# SW6121_Demo_board.net
KiCad netlist of a schematic drawn in Altium Designer
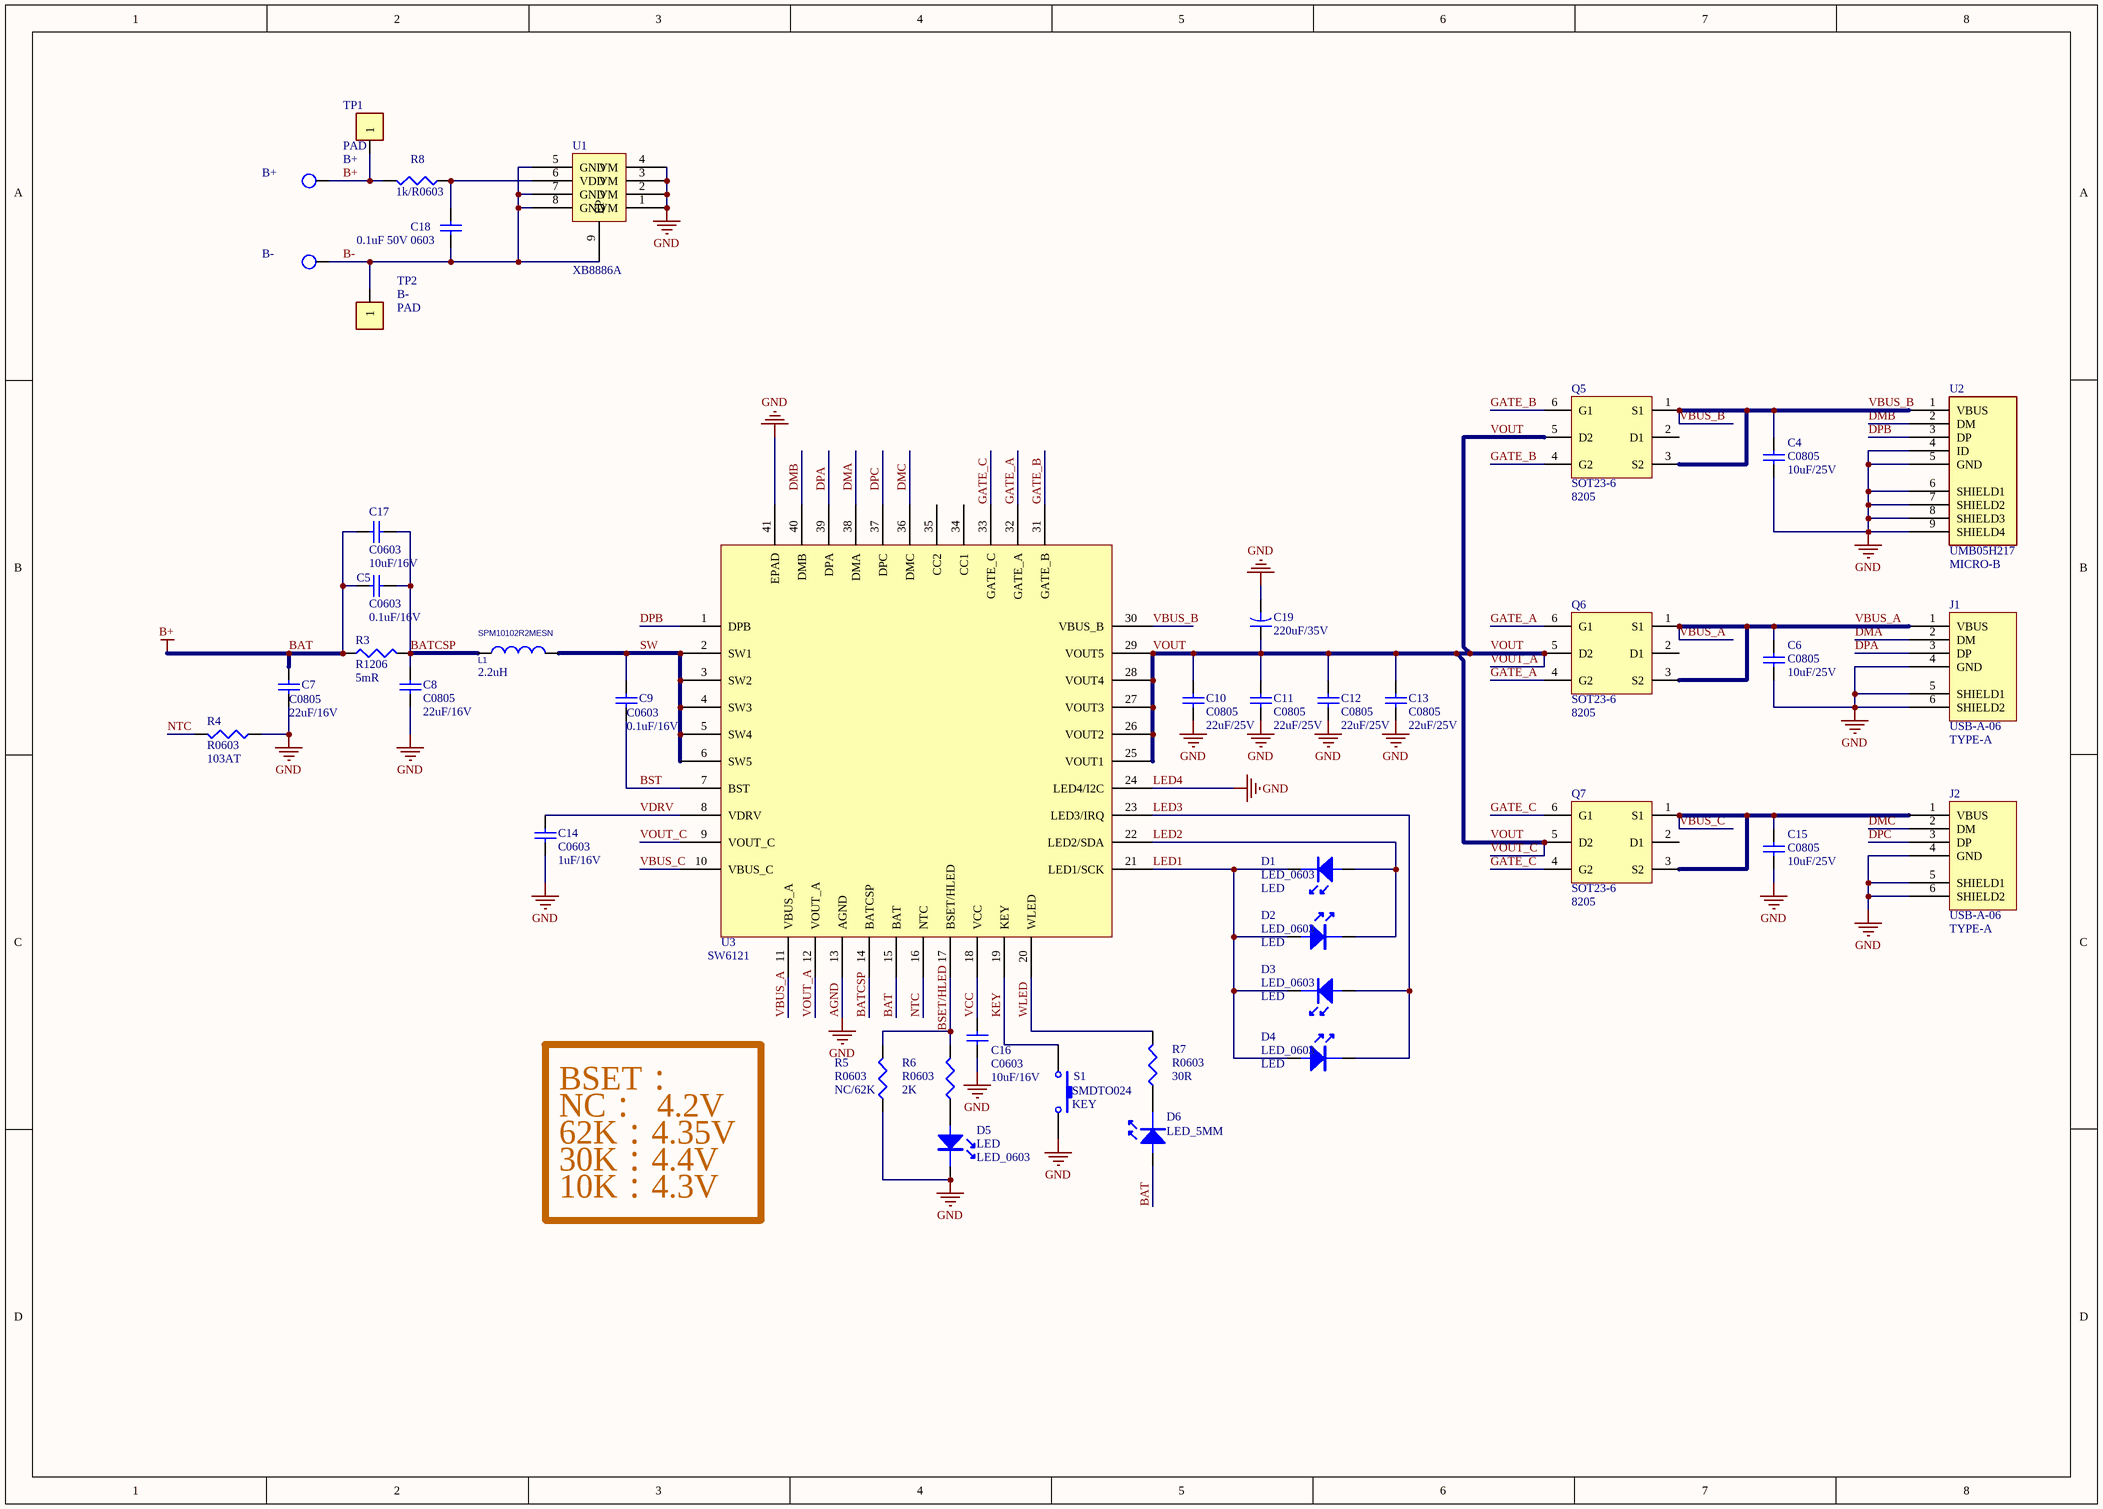
[diagram p0: SW6121 Demo board.SchDoc]

(export (version "E")
  (design (tool "Eeschema 10.0.6"))
  (components
    (comp (ref "B+") (value "PDA") (footprint "PAD") (libsource (lib "ZYX") (part "PDA")))
    (comp (ref "B-") (value "PDA") (footprint "PAD") (libsource (lib "ZYX") (part "PDA")))
    (comp (ref "C4")
      (value "C0805")
      (footprint "C0805")
      (description "Capacitor")
      (fields (field (name "ALTIUM_VALUE") "10uF/25V") (field (name "PUBLISHER") "Altium Limited"))
      (libsource (lib "*") (part "CAP0603"))
    )
    (comp (ref "C5")
      (value "C0603")
      (footprint "C0603")
      (description "Capacitor")
      (fields (field (name "ALTIUM_VALUE") "0.1uF/16V") (field (name "PUBLISHER") "Altium Limited"))
      (libsource (lib "*") (part "CAP0603"))
    )
    (comp (ref "C6")
      (value "C0805")
      (footprint "C0805")
      (description "Capacitor")
      (fields (field (name "ALTIUM_VALUE") "10uF/25V") (field (name "PUBLISHER") "Altium Limited"))
      (libsource (lib "*") (part "CAP0603"))
    )
    (comp (ref "C7")
      (value "C0805")
      (footprint "C0805")
      (description "Capacitor")
      (fields (field (name "ALTIUM_VALUE") "22uF/16V") (field (name "PUBLISHER") "Altium Limited"))
      (libsource (lib "*") (part "CAP0805"))
    )
    (comp (ref "C8")
      (value "C0805")
      (footprint "C0805")
      (description "Capacitor")
      (fields (field (name "ALTIUM_VALUE") "22uF/16V") (field (name "PUBLISHER") "Altium Limited"))
      (libsource (lib "*") (part "CAP0805"))
    )
    (comp (ref "C9")
      (value "C0603")
      (footprint "C0603")
      (description "Capacitor")
      (fields (field (name "ALTIUM_VALUE") "0.1uF/16V") (field (name "PUBLISHER") "Altium Limited"))
      (libsource (lib "*") (part "CAP0603"))
    )
    (comp (ref "C10")
      (value "C0805")
      (footprint "C0805")
      (description "Capacitor")
      (fields (field (name "ALTIUM_VALUE") "22uF/25V") (field (name "PUBLISHER") "Altium Limited"))
      (libsource (lib "*") (part "CAP0805"))
    )
    (comp (ref "C11")
      (value "C0805")
      (footprint "C0805")
      (description "Capacitor")
      (fields (field (name "ALTIUM_VALUE") "22uF/25V") (field (name "PUBLISHER") "Altium Limited"))
      (libsource (lib "*") (part "CAP0805"))
    )
    (comp (ref "C12")
      (value "C0805")
      (footprint "C0805")
      (description "Capacitor")
      (fields (field (name "ALTIUM_VALUE") "22uF/25V") (field (name "PUBLISHER") "Altium Limited"))
      (libsource (lib "*") (part "CAP0805"))
    )
    (comp (ref "C13")
      (value "C0805")
      (footprint "C0805")
      (description "Capacitor")
      (fields (field (name "ALTIUM_VALUE") "22uF/25V") (field (name "PUBLISHER") "Altium Limited"))
      (libsource (lib "*") (part "CAP0805"))
    )
    (comp (ref "C14")
      (value "C0603")
      (footprint "C0603")
      (description "Capacitor")
      (fields (field (name "ALTIUM_VALUE") "1uF/16V") (field (name "PUBLISHER") "Altium Limited"))
      (libsource (lib "*") (part "CAP0603"))
    )
    (comp (ref "C15")
      (value "C0805")
      (footprint "C0805")
      (description "Capacitor")
      (fields (field (name "ALTIUM_VALUE") "10uF/25V") (field (name "PUBLISHER") "Altium Limited"))
      (libsource (lib "*") (part "CAP0603"))
    )
    (comp (ref "C16")
      (value "C0603")
      (footprint "C0603")
      (description "Capacitor")
      (fields (field (name "ALTIUM_VALUE") "10uF/16V") (field (name "PUBLISHER") "Altium Limited"))
      (libsource (lib "*") (part "CAP0603"))
    )
    (comp (ref "C17")
      (value "C0603")
      (footprint "C0603")
      (description "Capacitor")
      (fields (field (name "ALTIUM_VALUE") "10uF/16V") (field (name "PUBLISHER") "Altium Limited"))
      (libsource (lib "*") (part "CAP0603"))
    )
    (comp (ref "C18") (value "0.1uF 50V 0603") (footprint "LIB:C0402") (libsource (lib "ZYX") (part "Cap")))
    (comp (ref "C19")
      (value "220uF/35V")
      (footprint "Cap  ( E )  6.5 * 12.0  Erect")
      (description "Electroytic Capacitor, 100uF/35V, ±20%, 105℃，Φ 6.5 * 12.0 mm")
      (fields (field (name "Comment") "E - Cap") (field (name "PUBLISHER") "Altium Limited"))
      (libsource (lib "D-lib") (part "E - Cap"))
    )
    (comp (ref "D1") (value "LED") (footprint "LED_0603") (libsource (lib "*") (part "LED")))
    (comp (ref "D2") (value "LED") (footprint "LED_0603") (libsource (lib "*") (part "LED")))
    (comp (ref "D3") (value "LED") (footprint "LED_0603") (libsource (lib "*") (part "LED")))
    (comp (ref "D4") (value "LED") (footprint "LED_0603") (libsource (lib "*") (part "LED")))
    (comp (ref "D5") (value "LED") (footprint "LED_0603") (libsource (lib "*") (part "LED")))
    (comp (ref "D6")
      (value "LED_5MM")
      (footprint "LED_5MM")
      (fields (field (name "FOOTPRINF") "LED_5MM"))
      (libsource (lib "*") (part "LED"))
    )
    (comp (ref "J1")
      (value "TYPE-A")
      (footprint "USB-A-06")
      (fields (field (name "FOOTPRINF") "USB-A-06") (field (name "Comment") "TYPE-A-1"))
      (libsource (lib "*") (part "TYPE-A-1"))
    )
    (comp (ref "J2")
      (value "TYPE-A")
      (footprint "USB-A-06")
      (fields (field (name "FOOTPRINF") "USB-A-06") (field (name "Comment") "TYPE-A-1"))
      (libsource (lib "*") (part "TYPE-A-1"))
    )
    (comp (ref "L1")
      (value "SPM10102R2MESN")
      (footprint "INDUCTOR_SPM1010")
      (fields (field (name "ALTIUM_VALUE") "2.2uH"))
      (libsource (lib "*") (part "INDUCTOR"))
    )
    (comp (ref "Q5")
      (value "8205")
      (footprint "SOT23-6")
      (fields (field (name "FOOTPRINF") "SOT23-6"))
      (libsource (lib "*") (part "8205B"))
    )
    (comp (ref "Q6")
      (value "8205")
      (footprint "SOT23-6")
      (fields (field (name "FOOTPRINF") "SOT23-6"))
      (libsource (lib "*") (part "8205B"))
    )
    (comp (ref "Q7")
      (value "8205")
      (footprint "SOT23-6")
      (fields (field (name "FOOTPRINF") "SOT23-6"))
      (libsource (lib "*") (part "8205B"))
    )
    (comp (ref "R3")
      (value "R1206")
      (footprint "R1206")
      (description "Resistor")
      (fields (field (name "ALTIUM_VALUE") "5mR") (field (name "PUBLISHER") "Altium Limited"))
      (libsource (lib "*") (part "RES"))
    )
    (comp (ref "R4")
      (value "R0603")
      (footprint "R0603")
      (description "Resistor")
      (fields (field (name "ALTIUM_VALUE") "103AT") (field (name "PUBLISHER") "Altium Limited"))
      (libsource (lib "*") (part "RES"))
    )
    (comp (ref "R5")
      (value "R0603")
      (footprint "R0603")
      (description "Resistor")
      (fields (field (name "ALTIUM_VALUE") "NC/62K") (field (name "PUBLISHER") "Altium Limited"))
      (libsource (lib "*") (part "RES"))
    )
    (comp (ref "R6")
      (value "R0603")
      (footprint "R0603")
      (description "Resistor")
      (fields (field (name "ALTIUM_VALUE") "2K") (field (name "PUBLISHER") "Altium Limited"))
      (libsource (lib "*") (part "RES"))
    )
    (comp (ref "R7")
      (value "R0603")
      (footprint "R0603")
      (description "Resistor")
      (fields (field (name "ALTIUM_VALUE") "30R") (field (name "PUBLISHER") "Altium Limited"))
      (libsource (lib "*") (part "RES"))
    )
    (comp (ref "R8")
      (value "1k/R0603")
      (footprint "R0402")
      (description "Resistor")
      (fields (field (name "PUBLISHER") "Altium Limited"))
      (libsource (lib "*") (part "RES"))
    )
    (comp (ref "S1")
      (value "KEY")
      (footprint "SMDTO024")
      (fields (field (name "FOOTPRINF") "SMDTO024"))
      (libsource (lib "*") (part "SW K"))
    )
    (comp (ref "TP1") (value "B+") (footprint "PAD") (libsource (lib "") (part "Test Point_1")))
    (comp (ref "TP2") (value "B-") (footprint "PAD") (libsource (lib "*") (part "Test Point")))
    (comp (ref "U1") (value "XB8886A") (footprint "SOP-8-G") (libsource (lib "ZYX") (part "XB8089")))
    (comp (ref "U2")
      (value "MICRO-B")
      (footprint "UMB05H217")
      (fields (field (name "FOOTPRINTF") "UMB05H217") (field (name "Comment") "USB_MICRO_B"))
      (libsource (lib "*") (part "USB_MICRO_B"))
    )
    (comp (ref "U3")
      (value "SW6121")
      (footprint "QFN40_EPAD_SW6124_6X6")
      (fields (field (name "Comment") "SW61201"))
      (libsource (lib "*") (part "SW6124"))
    )
  )
  (nets
    (net (code "1") (name "/B-") (class "Default")
      (node (ref "B-") (pin "0") (pintype "passive"))
      (node (ref "C18") (pin "1") (pinfunction "1_1") (pintype "passive"))
      (node (ref "TP2") (pin "1") (pinfunction "1_1") (pintype "passive"))
      (node (ref "U1") (pin "5") (pinfunction "GND_5") (pintype "passive"))
      (node (ref "U1") (pin "7") (pinfunction "GND_7") (pintype "passive"))
      (node (ref "U1") (pin "8") (pinfunction "GND_8") (pintype "passive"))
      (node (ref "U1") (pin "9") (pinfunction "EP_9") (pintype "passive"))
    )
    (net (code "2") (name "/BATCSP") (class "Default")
      (node (ref "C17") (pin "1") (pinfunction "1_1") (pintype "passive"))
      (node (ref "C5") (pin "2") (pinfunction "2_2") (pintype "passive"))
      (node (ref "C8") (pin "2") (pinfunction "2_2") (pintype "passive"))
      (node (ref "L1") (pin "1") (pinfunction "1_1") (pintype "passive"))
      (node (ref "R3") (pin "2") (pinfunction "2_2") (pintype "passive"))
      (node (ref "U3") (pin "14") (pinfunction "BATCSP_14") (pintype "passive"))
    )
    (net (code "3") (name "/BSET{slash}HLED") (class "Default")
      (node (ref "R5") (pin "2") (pinfunction "2_2") (pintype "passive"))
      (node (ref "R6") (pin "2") (pinfunction "2_2") (pintype "passive"))
      (node (ref "U3") (pin "17") (pinfunction "BSET/HLED_17") (pintype "passive"))
    )
    (net (code "4") (name "/BST") (class "Default")
      (node (ref "C9") (pin "1") (pinfunction "1_1") (pintype "passive"))
      (node (ref "U3") (pin "7") (pinfunction "BST_7") (pintype "passive"))
    )
    (net (code "5") (name "/DMA") (class "Default")
      (node (ref "J1") (pin "2") (pinfunction "DM_2") (pintype "passive"))
      (node (ref "U3") (pin "38") (pinfunction "DMA_38") (pintype "passive"))
    )
    (net (code "6") (name "/DMB") (class "Default")
      (node (ref "U2") (pin "2") (pinfunction "DM_2") (pintype "passive"))
      (node (ref "U3") (pin "40") (pinfunction "DMB_40") (pintype "passive"))
    )
    (net (code "7") (name "/DMC") (class "Default")
      (node (ref "J2") (pin "2") (pinfunction "DM_2") (pintype "passive"))
      (node (ref "U3") (pin "36") (pinfunction "DMC_36") (pintype "passive"))
    )
    (net (code "8") (name "/DPA") (class "Default")
      (node (ref "J1") (pin "3") (pinfunction "DP_3") (pintype "passive"))
      (node (ref "U3") (pin "39") (pinfunction "DPA_39") (pintype "passive"))
    )
    (net (code "9") (name "/DPB") (class "Default")
      (node (ref "U2") (pin "3") (pinfunction "DP_3") (pintype "passive"))
      (node (ref "U3") (pin "1") (pinfunction "DPB_1") (pintype "passive"))
    )
    (net (code "10") (name "/DPC") (class "Default")
      (node (ref "J2") (pin "3") (pinfunction "DP_3") (pintype "passive"))
      (node (ref "U3") (pin "37") (pinfunction "DPC_37") (pintype "passive"))
    )
    (net (code "11") (name "/GATE_A") (class "Default")
      (node (ref "Q6") (pin "4") (pinfunction "G2_4") (pintype "passive"))
      (node (ref "Q6") (pin "6") (pinfunction "G1_6") (pintype "passive"))
      (node (ref "U3") (pin "32") (pinfunction "GATE_A_32") (pintype "passive"))
    )
    (net (code "12") (name "/GATE_B") (class "Default")
      (node (ref "Q5") (pin "4") (pinfunction "G2_4") (pintype "passive"))
      (node (ref "Q5") (pin "6") (pinfunction "G1_6") (pintype "passive"))
      (node (ref "U3") (pin "31") (pinfunction "GATE_B_31") (pintype "passive"))
    )
    (net (code "13") (name "/GATE_C") (class "Default")
      (node (ref "Q7") (pin "4") (pinfunction "G2_4") (pintype "passive"))
      (node (ref "Q7") (pin "6") (pinfunction "G1_6") (pintype "passive"))
      (node (ref "U3") (pin "33") (pinfunction "GATE_C_33") (pintype "passive"))
    )
    (net (code "14") (name "/KEY") (class "Default")
      (node (ref "S1") (pin "1") (pinfunction "1_1") (pintype "passive"))
      (node (ref "U3") (pin "19") (pinfunction "KEY_19") (pintype "passive"))
    )
    (net (code "15") (name "/LED1") (class "Default")
      (node (ref "D1") (pin "2") (pinfunction "K_2") (pintype "passive"))
      (node (ref "D2") (pin "1") (pinfunction "A_1") (pintype "passive"))
      (node (ref "D3") (pin "2") (pinfunction "K_2") (pintype "passive"))
      (node (ref "D4") (pin "1") (pinfunction "A_1") (pintype "passive"))
      (node (ref "U3") (pin "21") (pinfunction "LED1/SCK_21") (pintype "passive"))
    )
    (net (code "16") (name "/LED2") (class "Default")
      (node (ref "D1") (pin "1") (pinfunction "A_1") (pintype "passive"))
      (node (ref "D2") (pin "2") (pinfunction "K_2") (pintype "passive"))
      (node (ref "U3") (pin "22") (pinfunction "LED2/SDA_22") (pintype "passive"))
    )
    (net (code "17") (name "/LED3") (class "Default")
      (node (ref "D3") (pin "1") (pinfunction "A_1") (pintype "passive"))
      (node (ref "D4") (pin "2") (pinfunction "K_2") (pintype "passive"))
      (node (ref "U3") (pin "23") (pinfunction "LED3/IRQ_23") (pintype "passive"))
    )
    (net (code "18") (name "/NTC") (class "Default")
      (node (ref "R4") (pin "2") (pinfunction "2_2") (pintype "passive"))
      (node (ref "U3") (pin "16") (pinfunction "NTC_16") (pintype "passive"))
    )
    (net (code "19") (name "/SW") (class "Default")
      (node (ref "C9") (pin "2") (pinfunction "2_2") (pintype "passive"))
      (node (ref "L1") (pin "2") (pinfunction "2_2") (pintype "passive"))
      (node (ref "U3") (pin "2") (pinfunction "SW1_2") (pintype "passive"))
      (node (ref "U3") (pin "3") (pinfunction "SW2_3") (pintype "passive"))
      (node (ref "U3") (pin "4") (pinfunction "SW3_4") (pintype "passive"))
      (node (ref "U3") (pin "5") (pinfunction "SW4_5") (pintype "passive"))
      (node (ref "U3") (pin "6") (pinfunction "SW5_6") (pintype "passive"))
    )
    (net (code "20") (name "/VBUS_A") (class "Default")
      (node (ref "C6") (pin "2") (pinfunction "2_2") (pintype "passive"))
      (node (ref "J1") (pin "1") (pinfunction "VBUS_1") (pintype "passive"))
      (node (ref "Q6") (pin "1") (pinfunction "S1_1") (pintype "passive"))
      (node (ref "Q6") (pin "3") (pinfunction "S2_3") (pintype "passive"))
      (node (ref "U3") (pin "11") (pinfunction "VBUS_A_11") (pintype "passive"))
    )
    (net (code "21") (name "/VBUS_B") (class "Default")
      (node (ref "C4") (pin "2") (pinfunction "2_2") (pintype "passive"))
      (node (ref "Q5") (pin "1") (pinfunction "S1_1") (pintype "passive"))
      (node (ref "Q5") (pin "3") (pinfunction "S2_3") (pintype "passive"))
      (node (ref "U2") (pin "1") (pinfunction "VBUS_1") (pintype "passive"))
      (node (ref "U3") (pin "30") (pinfunction "VBUS_B_30") (pintype "passive"))
    )
    (net (code "22") (name "/VBUS_C") (class "Default")
      (node (ref "C15") (pin "2") (pinfunction "2_2") (pintype "passive"))
      (node (ref "J2") (pin "1") (pinfunction "VBUS_1") (pintype "passive"))
      (node (ref "Q7") (pin "1") (pinfunction "S1_1") (pintype "passive"))
      (node (ref "Q7") (pin "3") (pinfunction "S2_3") (pintype "passive"))
      (node (ref "U3") (pin "10") (pinfunction "VBUS_C_10") (pintype "passive"))
    )
    (net (code "23") (name "/VCC") (class "Default")
      (node (ref "C16") (pin "2") (pinfunction "2_2") (pintype "passive"))
      (node (ref "U3") (pin "18") (pinfunction "VCC_18") (pintype "passive"))
    )
    (net (code "24") (name "/VDRV") (class "Default")
      (node (ref "C14") (pin "2") (pinfunction "2_2") (pintype "passive"))
      (node (ref "U3") (pin "8") (pinfunction "VDRV_8") (pintype "passive"))
    )
    (net (code "25") (name "/VOUT") (class "Default")
      (node (ref "C10") (pin "2") (pinfunction "2_2") (pintype "passive"))
      (node (ref "C11") (pin "2") (pinfunction "2_2") (pintype "passive"))
      (node (ref "C12") (pin "2") (pinfunction "2_2") (pintype "passive"))
      (node (ref "C13") (pin "2") (pinfunction "2_2") (pintype "passive"))
      (node (ref "C19") (pin "1") (pinfunction "1_1") (pintype "passive"))
      (node (ref "Q5") (pin "5") (pinfunction "D2_5") (pintype "passive"))
      (node (ref "Q6") (pin "5") (pinfunction "D2_5") (pintype "passive"))
      (node (ref "Q7") (pin "5") (pinfunction "D2_5") (pintype "passive"))
      (node (ref "U3") (pin "12") (pinfunction "VOUT_A_12") (pintype "passive"))
      (node (ref "U3") (pin "25") (pinfunction "VOUT1_25") (pintype "passive"))
      (node (ref "U3") (pin "26") (pinfunction "VOUT2_26") (pintype "passive"))
      (node (ref "U3") (pin "27") (pinfunction "VOUT3_27") (pintype "passive"))
      (node (ref "U3") (pin "28") (pinfunction "VOUT4_28") (pintype "passive"))
      (node (ref "U3") (pin "29") (pinfunction "VOUT5_29") (pintype "passive"))
      (node (ref "U3") (pin "9") (pinfunction "VOUT_C_9") (pintype "passive"))
    )
    (net (code "26") (name "/WLED") (class "Default")
      (node (ref "R7") (pin "2") (pinfunction "2_2") (pintype "passive"))
      (node (ref "U3") (pin "20") (pinfunction "WLED_20") (pintype "passive"))
    )
    (net (code "27") (name "B+") (class "Default")
      (node (ref "B+") (pin "0") (pintype "passive"))
      (node (ref "C17") (pin "2") (pinfunction "2_2") (pintype "passive"))
      (node (ref "C5") (pin "1") (pinfunction "1_1") (pintype "passive"))
      (node (ref "C7") (pin "2") (pinfunction "2_2") (pintype "passive"))
      (node (ref "D6") (pin "1") (pinfunction "A_1") (pintype "passive"))
      (node (ref "R3") (pin "1") (pinfunction "1_1") (pintype "passive"))
      (node (ref "R8") (pin "2") (pinfunction "2_2") (pintype "passive"))
      (node (ref "TP1") (pin "1") (pinfunction "1_1") (pintype "passive"))
      (node (ref "U3") (pin "15") (pinfunction "BAT_15") (pintype "passive"))
    )
    (net (code "28") (name "GND") (class "Default")
      (node (ref "C10") (pin "1") (pinfunction "1_1") (pintype "passive"))
      (node (ref "C11") (pin "1") (pinfunction "1_1") (pintype "passive"))
      (node (ref "C12") (pin "1") (pinfunction "1_1") (pintype "passive"))
      (node (ref "C13") (pin "1") (pinfunction "1_1") (pintype "passive"))
      (node (ref "C14") (pin "1") (pinfunction "1_1") (pintype "passive"))
      (node (ref "C15") (pin "1") (pinfunction "1_1") (pintype "passive"))
      (node (ref "C16") (pin "1") (pinfunction "1_1") (pintype "passive"))
      (node (ref "C19") (pin "2") (pinfunction "2_2") (pintype "passive"))
      (node (ref "C4") (pin "1") (pinfunction "1_1") (pintype "passive"))
      (node (ref "C6") (pin "1") (pinfunction "1_1") (pintype "passive"))
      (node (ref "C7") (pin "1") (pinfunction "1_1") (pintype "passive"))
      (node (ref "C8") (pin "1") (pinfunction "1_1") (pintype "passive"))
      (node (ref "D5") (pin "2") (pinfunction "K_2") (pintype "passive"))
      (node (ref "J1") (pin "4") (pinfunction "GND_4") (pintype "passive"))
      (node (ref "J1") (pin "5") (pinfunction "SHIELD1_5") (pintype "passive"))
      (node (ref "J1") (pin "6") (pinfunction "SHIELD2_6") (pintype "passive"))
      (node (ref "J2") (pin "4") (pinfunction "GND_4") (pintype "passive"))
      (node (ref "J2") (pin "5") (pinfunction "SHIELD1_5") (pintype "passive"))
      (node (ref "J2") (pin "6") (pinfunction "SHIELD2_6") (pintype "passive"))
      (node (ref "R4") (pin "1") (pinfunction "1_1") (pintype "passive"))
      (node (ref "R5") (pin "1") (pinfunction "1_1") (pintype "passive"))
      (node (ref "S1") (pin "2") (pinfunction "2_2") (pintype "passive"))
      (node (ref "U1") (pin "1") (pinfunction "VM_1") (pintype "passive"))
      (node (ref "U1") (pin "2") (pinfunction "VM_2") (pintype "passive"))
      (node (ref "U1") (pin "3") (pinfunction "VM_3") (pintype "passive"))
      (node (ref "U1") (pin "4") (pinfunction "VM_4") (pintype "passive"))
      (node (ref "U2") (pin "4") (pinfunction "ID_4") (pintype "passive"))
      (node (ref "U2") (pin "5") (pinfunction "GND_5") (pintype "passive"))
      (node (ref "U2") (pin "6") (pinfunction "SHIELD1_6") (pintype "passive"))
      (node (ref "U2") (pin "7") (pinfunction "SHIELD2_7") (pintype "passive"))
      (node (ref "U2") (pin "8") (pinfunction "SHIELD3_8") (pintype "passive"))
      (node (ref "U2") (pin "9") (pinfunction "SHIELD4_9") (pintype "passive"))
      (node (ref "U3") (pin "13") (pinfunction "AGND_13") (pintype "passive"))
      (node (ref "U3") (pin "24") (pinfunction "LED4/I2C_24") (pintype "passive"))
      (node (ref "U3") (pin "41") (pinfunction "EPAD_41") (pintype "passive"))
    )
    (net (code "29") (name "Net-(D5-A)") (class "Default")
      (node (ref "D5") (pin "1") (pinfunction "A_1") (pintype "passive"))
      (node (ref "R6") (pin "1") (pinfunction "1_1") (pintype "passive"))
    )
    (net (code "30") (name "Net-(D6-K)") (class "Default")
      (node (ref "D6") (pin "2") (pinfunction "K_2") (pintype "passive"))
      (node (ref "R7") (pin "1") (pinfunction "1_1") (pintype "passive"))
    )
    (net (code "31") (name "Net-(U1-VDD)") (class "Default")
      (node (ref "C18") (pin "0") (pinfunction "0_0") (pintype "passive"))
      (node (ref "R8") (pin "1") (pinfunction "1_1") (pintype "passive"))
      (node (ref "U1") (pin "6") (pinfunction "VDD_6") (pintype "passive"))
    )
    (net (code "32") (name "unconnected-(Q5-D1-Pad2)") (class "Default")
      (node (ref "Q5") (pin "2") (pinfunction "D1_2") (pintype "passive"))
    )
    (net (code "33") (name "unconnected-(Q6-D1-Pad2)") (class "Default")
      (node (ref "Q6") (pin "2") (pinfunction "D1_2") (pintype "passive"))
    )
    (net (code "34") (name "unconnected-(Q7-D1-Pad2)") (class "Default")
      (node (ref "Q7") (pin "2") (pinfunction "D1_2") (pintype "passive"))
    )
    (net (code "35") (name "unconnected-(U3-CC1-Pad34)") (class "Default")
      (node (ref "U3") (pin "34") (pinfunction "CC1_34") (pintype "passive"))
    )
    (net (code "36") (name "unconnected-(U3-CC2-Pad35)") (class "Default")
      (node (ref "U3") (pin "35") (pinfunction "CC2_35") (pintype "passive"))
    )
  )
)
